# ADC.net
KiCad netlist of a schematic drawn in Altium Designer
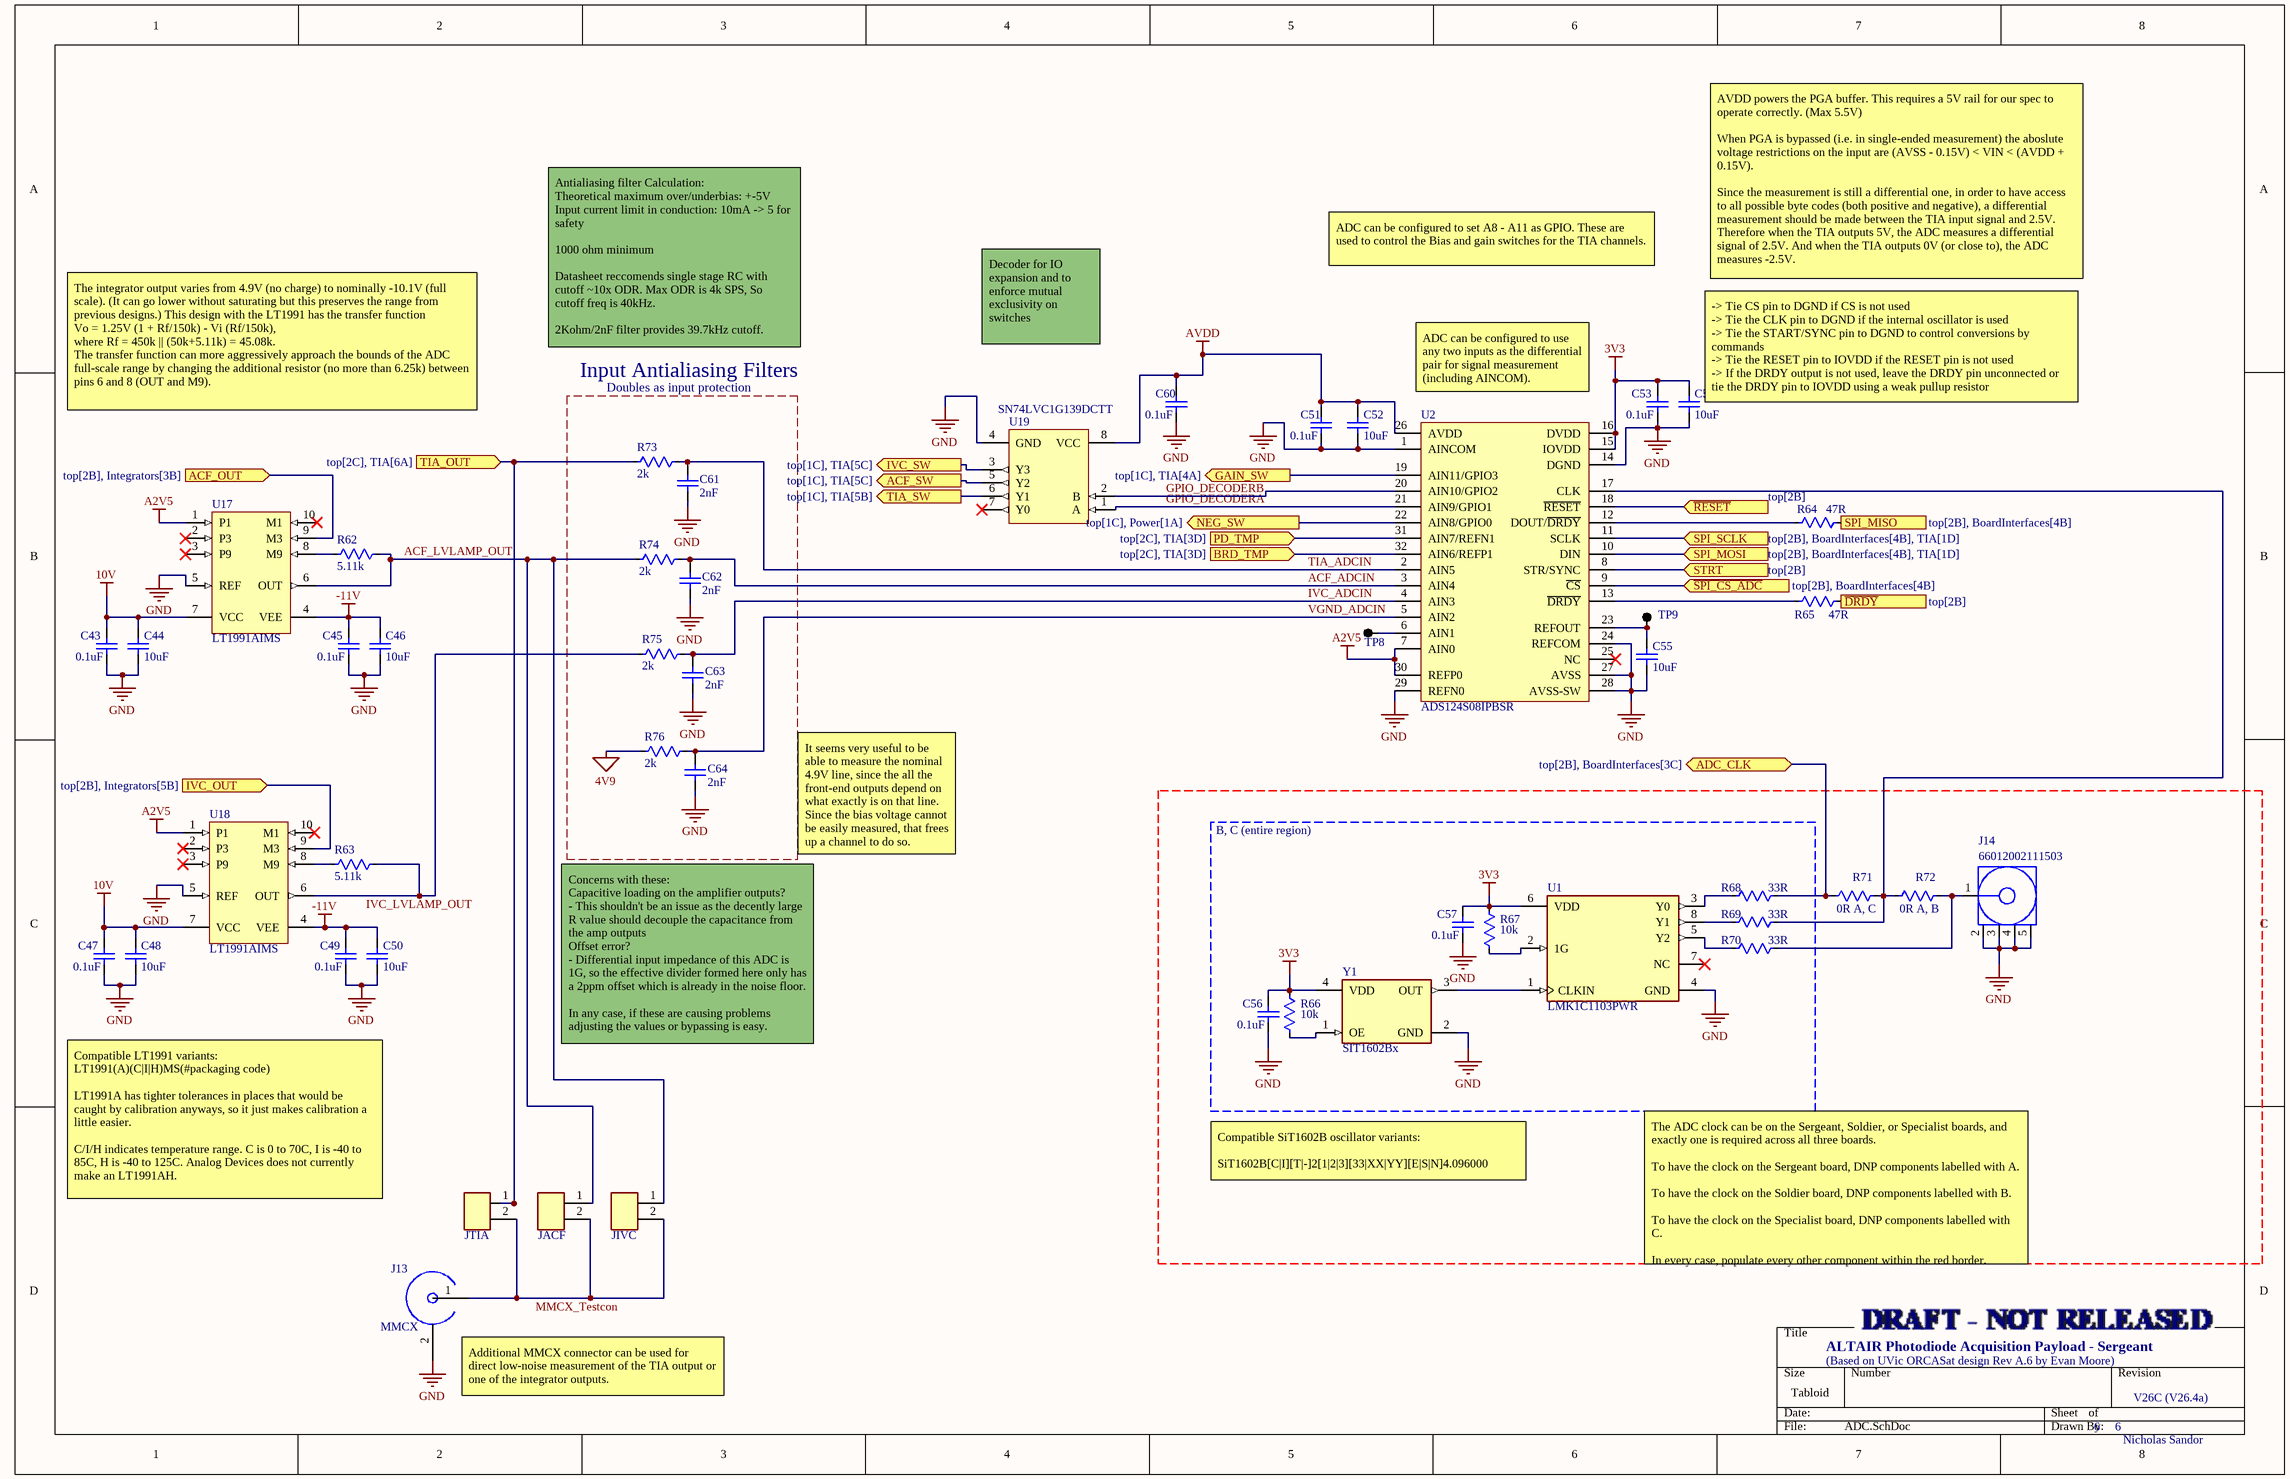
[diagram p0: ADC.SchDoc]

(export (version "E")
  (design (tool "Eeschema 10.0.6"))
  (components
    (comp (ref "C43")
      (value "0.1uF")
      (footprint "CAP 0603 NON-IPC KEMET X7R")
      (description "Kemet C0603C104K5RACAUTO - Cap Ceramic 0.1uF 50V X7R 10% 0603 125C Paper T/R")
      (fields (field (name "MF") "Kemet") (field (name "MP") "C0603C104K5RACAUTO"))
      (libsource (lib "ALTAIR_PD_Capacitors") (part "CAP"))
    )
    (comp (ref "C44")
      (value "10uF")
      (footprint "CAP 0805 IPC MID DENSITY")
      (description "Murata GRM21BR61E106KA73L - Cap Ceramic 10uF 10% 25V X5R 0805")
      (fields (field (name "MF") "Murata") (field (name "MP") "GRM21BR61E106KA73L"))
      (libsource (lib "ALTAIR_PD_Capacitors") (part "CAP"))
    )
    (comp (ref "C45")
      (value "0.1uF")
      (footprint "CAP 0603 NON-IPC KEMET X7R")
      (description "Kemet C0603C104K5RACAUTO - Cap Ceramic 0.1uF 50V X7R 10% 0603 125C Paper T/R")
      (fields (field (name "MF") "Kemet") (field (name "MP") "C0603C104K5RACAUTO"))
      (libsource (lib "ALTAIR_PD_Capacitors") (part "CAP"))
    )
    (comp (ref "C46")
      (value "10uF")
      (footprint "CAP 0805 IPC MID DENSITY")
      (description "Murata GRM21BR61E106KA73L - Cap Ceramic 10uF 10% 25V X5R 0805")
      (fields (field (name "MF") "Murata") (field (name "MP") "GRM21BR61E106KA73L"))
      (libsource (lib "ALTAIR_PD_Capacitors") (part "CAP"))
    )
    (comp (ref "C47")
      (value "0.1uF")
      (footprint "CAP 0603 NON-IPC KEMET X7R")
      (description "Kemet C0603C104K5RACAUTO - Cap Ceramic 0.1uF 50V X7R 10% 0603 125C Paper T/R")
      (fields (field (name "MF") "Kemet") (field (name "MP") "C0603C104K5RACAUTO"))
      (libsource (lib "ALTAIR_PD_Capacitors") (part "CAP"))
    )
    (comp (ref "C48")
      (value "10uF")
      (footprint "CAP 0805 IPC MID DENSITY")
      (description "Murata GRM21BR61E106KA73L - Cap Ceramic 10uF 10% 25V X5R 0805")
      (fields (field (name "MF") "Murata") (field (name "MP") "GRM21BR61E106KA73L"))
      (libsource (lib "ALTAIR_PD_Capacitors") (part "CAP"))
    )
    (comp (ref "C49")
      (value "0.1uF")
      (footprint "CAP 0603 NON-IPC KEMET X7R")
      (description "Kemet C0603C104K5RACAUTO - Cap Ceramic 0.1uF 50V X7R 10% 0603 125C Paper T/R")
      (fields (field (name "MF") "Kemet") (field (name "MP") "C0603C104K5RACAUTO"))
      (libsource (lib "ALTAIR_PD_Capacitors") (part "CAP"))
    )
    (comp (ref "C50")
      (value "10uF")
      (footprint "CAP 0805 IPC MID DENSITY")
      (description "Murata GRM21BR61E106KA73L - Cap Ceramic 10uF 10% 25V X5R 0805")
      (fields (field (name "MF") "Murata") (field (name "MP") "GRM21BR61E106KA73L"))
      (libsource (lib "ALTAIR_PD_Capacitors") (part "CAP"))
    )
    (comp (ref "C51")
      (value "0.1uF")
      (footprint "CAP 0603 IPC MID DENSITY")
      (description "Kemet C0603C104K5RACAUTO - Cap Ceramic 0.1uF 50V X7R 10% 0603 125C Paper T/R")
      (fields (field (name "MF") "Kemet") (field (name "MP") "C0603C104K5RACAUTO"))
      (libsource (lib "ALTAIR_PD_Capacitors") (part "CAP"))
    )
    (comp (ref "C52")
      (value "10uF")
      (footprint "CAP 0805 IPC MID DENSITY")
      (description "Murata GRM21BR61E106KA73L - Cap Ceramic 10uF 10% 25V X5R 0805")
      (fields (field (name "MF") "Murata") (field (name "MP") "GRM21BR61E106KA73L"))
      (libsource (lib "ALTAIR_PD_Capacitors") (part "CAP"))
    )
    (comp (ref "C53")
      (value "0.1uF")
      (footprint "CAP 0603 IPC MID DENSITY")
      (description "Kemet C0603C104K5RACAUTO - Cap Ceramic 0.1uF 50V X7R 10% 0603 125C Paper T/R")
      (fields (field (name "MF") "Kemet") (field (name "MP") "C0603C104K5RACAUTO"))
      (libsource (lib "ALTAIR_PD_Capacitors") (part "CAP"))
    )
    (comp (ref "C54")
      (value "10uF")
      (footprint "CAP 0805 IPC MID DENSITY")
      (description "Murata GRM21BR61E106KA73L - Cap Ceramic 10uF 10% 25V X5R 0805")
      (fields (field (name "MF") "Murata") (field (name "MP") "GRM21BR61E106KA73L"))
      (libsource (lib "ALTAIR_PD_Capacitors") (part "CAP"))
    )
    (comp (ref "C55")
      (value "10uF")
      (footprint "CAP 0805 IPC MID DENSITY")
      (description "Murata GRM21BR61E106KA73L - Cap Ceramic 10uF 10% 25V X5R 0805")
      (fields (field (name "MF") "Murata") (field (name "MP") "GRM21BR61E106KA73L"))
      (libsource (lib "ALTAIR_PD_Capacitors") (part "CAP"))
    )
    (comp (ref "C56")
      (value "0.1uF")
      (footprint "CAP 0603 IPC MID DENSITY")
      (description "Kemet C0603C104K5RACAUTO - Cap Ceramic 0.1uF 50V X7R 10% 0603 125C Paper T/R")
      (fields (field (name "MF") "Kemet") (field (name "MP") "C0603C104K5RACAUTO"))
      (libsource (lib "ALTAIR_PD_Capacitors") (part "CAP"))
    )
    (comp (ref "C57")
      (value "0.1uF")
      (footprint "CAP 0603 IPC MID DENSITY")
      (description "Kemet C0603C104K5RACAUTO - Cap Ceramic 0.1uF 50V X7R 10% 0603 125C Paper T/R")
      (fields (field (name "MF") "Kemet") (field (name "MP") "C0603C104K5RACAUTO"))
      (libsource (lib "ALTAIR_PD_Capacitors") (part "CAP"))
    )
    (comp (ref "C60")
      (value "0.1uF")
      (footprint "CAP 0603 IPC MID DENSITY")
      (description "Kemet C0603C104K5RACAUTO - Cap Ceramic 0.1uF 50V X7R 10% 0603 125C Paper T/R")
      (fields (field (name "MF") "Kemet") (field (name "MP") "C0603C104K5RACAUTO"))
      (libsource (lib "ALTAIR_PD_Capacitors") (part "CAP"))
    )
    (comp (ref "C61")
      (value "2nF")
      (footprint "CAP 0603 IPC MID DENSITY")
      (description "Cap, Nonpolar, Any, Must choose footprint manually")
      (libsource (lib "ALTAIR_PD_Capacitors") (part "CAP"))
    )
    (comp (ref "C62")
      (value "2nF")
      (footprint "CAP 0603 IPC MID DENSITY")
      (description "Cap, Nonpolar, Any, Must choose footprint manually")
      (libsource (lib "ALTAIR_PD_Capacitors") (part "CAP"))
    )
    (comp (ref "C63")
      (value "2nF")
      (footprint "CAP 0603 IPC MID DENSITY")
      (description "Cap, Nonpolar, Any, Must choose footprint manually")
      (libsource (lib "ALTAIR_PD_Capacitors") (part "CAP"))
    )
    (comp (ref "C64")
      (value "2nF")
      (footprint "CAP 0603 IPC MID DENSITY")
      (description "Cap, Nonpolar, Any, Must choose footprint manually")
      (libsource (lib "ALTAIR_PD_Capacitors") (part "CAP"))
    )
    (comp (ref "J13")
      (value "MMCX")
      (footprint "COAX MMCX SMD")
      (description "Conn MMCX F 50Ohm Solder ST SMD Gold Tray")
      (fields (field (name "MF") "Molex") (field (name "MP") "0734152061"))
      (libsource (lib "ALTAIR_PD_Coaxial") (part "MMCX_recp"))
    )
    (comp (ref "J14")
      (value "66012002111503")
      (footprint "COAX MMCX THT")
      (description "Rf Coaxial, Mmcx Jack, 50 Ohm, Pcb Rohs Compliant: Yes ¦Wurth Elektronik 66012002111503")
      (fields (field (name "MF") "Wurth Elektronik"))
      (libsource (lib "ALTAIR_PD_Coaxial") (part "CMP-207975-000001-3"))
    )
    (comp (ref "JACF")
      (value "JACF")
      (footprint "ALTAIR_PD_Headers:JUMPER 2POS 1MM PITCH THT")
      (description "2x1 Header THT 1mm Pitch")
      (fields
        (field (name "MF") "GCT (GLOBAL CONNECTOR TECHNOLOGY)")
        (field (name "MP") "BC020-02-A-0200-0300-L-G")
      )
      (libsource (lib "ALTAIR_PD_Headers") (part "BC020-02-A-0200-0300-L-G"))
    )
    (comp (ref "JIVC")
      (value "JIVC")
      (footprint "ALTAIR_PD_Headers:JUMPER 2POS 1MM PITCH THT")
      (description "2x1 Header THT 1mm Pitch")
      (fields
        (field (name "MF") "GCT (GLOBAL CONNECTOR TECHNOLOGY)")
        (field (name "MP") "BC020-02-A-0200-0300-L-G")
      )
      (libsource (lib "ALTAIR_PD_Headers") (part "BC020-02-A-0200-0300-L-G"))
    )
    (comp (ref "JTIA")
      (value "JTIA")
      (footprint "ALTAIR_PD_Headers:JUMPER 2POS 1MM PITCH THT")
      (description "2x1 Header THT 1mm Pitch")
      (fields
        (field (name "MF") "GCT (GLOBAL CONNECTOR TECHNOLOGY)")
        (field (name "MP") "BC020-02-A-0200-0300-L-G")
      )
      (libsource (lib "ALTAIR_PD_Headers") (part "BC020-02-A-0200-0300-L-G"))
    )
    (comp (ref "R62")
      (value "5.11k")
      (footprint "RES 0402 IPC MID DENSITY")
      (description "Panasonic ERA-2AEB5111X - Res 5.11k 0.1% 1/16W SMD 0402")
      (fields (field (name "MF") "Panasonic Electronic Components") (field (name "MP") "ERA-2AEB5111X"))
      (libsource (lib "ALTAIR_PD_Resistors") (part "RES"))
    )
    (comp (ref "R63")
      (value "5.11k")
      (footprint "RES 0402 IPC MID DENSITY")
      (description "Panasonic ERA-2AEB5111X - Res 5.11k 0.1% 1/16W SMD 0402")
      (fields (field (name "MF") "Panasonic Electronic Components") (field (name "MP") "ERA-2AEB5111X"))
      (libsource (lib "ALTAIR_PD_Resistors") (part "RES"))
    )
    (comp (ref "R64")
      (value "47R")
      (footprint "RES 0402 NON-IPC SEI")
      (description "Stackpole RMCF0402JT47R0 - Res 47Ohm 5% 0.063W 0402 Thick Film AEC-Q200 compliant")
      (fields (field (name "MF") "Stackpole Electronics Inc.") (field (name "MP") "RMCF0402JT47R0"))
      (libsource (lib "ALTAIR_PD_Resistors") (part "RES"))
    )
    (comp (ref "R65")
      (value "47R")
      (footprint "RES 0402 NON-IPC SEI")
      (description "Stackpole RMCF0402JT47R0 - Res 47Ohm 5% 0.063W 0402 Thick Film AEC-Q200 compliant")
      (fields (field (name "MF") "Stackpole Electronics Inc.") (field (name "MP") "RMCF0402JT47R0"))
      (libsource (lib "ALTAIR_PD_Resistors") (part "RES"))
    )
    (comp (ref "R66")
      (value "10k")
      (footprint "RES 0603 IPC MID DENSITY")
      (description "Vishay CRCW060310K0FKEA SMD 0603 10k, CRCW e3 Series, 75V, thick film, 100mW")
      (fields (field (name "MF") "Vishay Dale") (field (name "MP") "CRCW060310K0FKEA"))
      (libsource (lib "ALTAIR_PD_Resistors") (part "RES"))
    )
    (comp (ref "R67")
      (value "10k")
      (footprint "RES 0603 IPC MID DENSITY")
      (description "Vishay CRCW060310K0FKEA SMD 0603 10k, CRCW e3 Series, 75V, thick film, 100mW")
      (fields (field (name "MF") "Vishay Dale") (field (name "MP") "CRCW060310K0FKEA"))
      (libsource (lib "ALTAIR_PD_Resistors") (part "RES"))
    )
    (comp (ref "R68")
      (value "33R")
      (footprint "RES 0402 NON-IPC YAGEO")
      (description "Yageo RC0402FR-0733RL - Res 33Ohm 1% 1/16W 0402")
      (fields (field (name "MF") "YAGEO") (field (name "MP") "RC0402FR-0733RL"))
      (libsource (lib "ALTAIR_PD_Resistors") (part "RES"))
    )
    (comp (ref "R69")
      (value "33R")
      (footprint "RES 0402 NON-IPC YAGEO")
      (description "Yageo RC0402FR-0733RL - Res 33Ohm 1% 1/16W 0402")
      (fields (field (name "MF") "YAGEO") (field (name "MP") "RC0402FR-0733RL"))
      (libsource (lib "ALTAIR_PD_Resistors") (part "RES"))
    )
    (comp (ref "R70")
      (value "33R")
      (footprint "RES 0402 NON-IPC YAGEO")
      (description "Yageo RC0402FR-0733RL - Res 33Ohm 1% 1/16W 0402")
      (fields (field (name "MF") "YAGEO") (field (name "MP") "RC0402FR-0733RL"))
      (libsource (lib "ALTAIR_PD_Resistors") (part "RES"))
    )
    (comp (ref "R71")
      (value "0R A, C")
      (footprint "RES 0402 IPC MID DENSITY")
      (description "Yageo RC0402JR-070RL - Res 0 Ohms 1/16W SMD 0402")
      (fields (field (name "MF") "YAGEO") (field (name "MP") "RC0402JR-070RL"))
      (libsource (lib "ALTAIR_PD_Resistors") (part "RES"))
    )
    (comp (ref "R72")
      (value "0R A, B")
      (footprint "RES 0402 IPC MID DENSITY")
      (description "Yageo RC0402JR-070RL - Res 0 Ohms 1/16W SMD 0402")
      (fields (field (name "MF") "YAGEO") (field (name "MP") "RC0402JR-070RL"))
      (libsource (lib "ALTAIR_PD_Resistors") (part "RES"))
    )
    (comp (ref "R73")
      (value "2k")
      (footprint "RES 0402 IPC MID DENSITY")
      (description "Res, Any, Manually select footprint")
      (libsource (lib "ALTAIR_PD_Resistors") (part "RES"))
    )
    (comp (ref "R74")
      (value "2k")
      (footprint "RES 0402 IPC MID DENSITY")
      (description "Res, Any, Manually select footprint")
      (libsource (lib "ALTAIR_PD_Resistors") (part "RES"))
    )
    (comp (ref "R75")
      (value "2k")
      (footprint "RES 0402 IPC MID DENSITY")
      (description "Res, Any, Manually select footprint")
      (libsource (lib "ALTAIR_PD_Resistors") (part "RES"))
    )
    (comp (ref "R76")
      (value "2k")
      (footprint "RES 0402 IPC MID DENSITY")
      (description "Res, Any, Manually select footprint")
      (libsource (lib "ALTAIR_PD_Resistors") (part "RES"))
    )
    (comp (ref "TP8")
      (value "Testpoint")
      (footprint "TESTPOINT THT")
      (libsource (lib "ALTAIR_PD_Testpoint") (part "Testpoint"))
    )
    (comp (ref "TP9")
      (value "Testpoint")
      (footprint "TESTPOINT THT")
      (libsource (lib "ALTAIR_PD_Testpoint") (part "Testpoint"))
    )
    (comp (ref "U1")
      (value "LMK1C1103PWR")
      (footprint "8-TSSOP 0.65MM PITCH 4.4MM WIDTH IPC MID DENSITY")
      (description "LVCMOS CLOCK BUFFER 3-CHANNEL")
      (fields (field (name "MF") "Texas Instruments"))
      (libsource (lib "ALTAIR_PD_ClockParts") (part "LMK1C1103PWR"))
    )
    (comp (ref "U2")
      (value "ADS124S08IPBSR")
      (footprint "32TQFP 7X7MM IPC LOW DENSITY")
      (description "24BIT ADC Delta-Sigma 4k samples/s PGA V-reference")
      (fields (field (name "MF") "Texas Instruments"))
      (libsource (lib "ALTAIR_PD_ADCs") (part "ADS124S08IPBSR"))
    )
    (comp (ref "U17")
      (value "LT1991AIMS")
      (footprint "10-SOP 0.5MM PITCH 3MM WIDTH IPC HIGH DENSITY")
      (fields
        (field (name "MF") "Linear Technology")
        (field (name "MP") "LT1991AIMS#PBF")
        (field (name "LINEAR TECHNOLOGY PART NUMBER") "LT1991")
      )
      (libsource (lib "ALTAIR_PD_Amplifiers") (part "LT1991IMS#TRPBF"))
    )
    (comp (ref "U18")
      (value "LT1991AIMS")
      (footprint "10-SOP 0.5MM PITCH 3MM WIDTH IPC HIGH DENSITY")
      (fields
        (field (name "MF") "Linear Technology")
        (field (name "MP") "LT1991AIMS#PBF")
        (field (name "LINEAR TECHNOLOGY PART NUMBER") "LT1991")
      )
      (libsource (lib "ALTAIR_PD_Amplifiers") (part "LT1991IMS#TRPBF"))
    )
    (comp (ref "U19")
      (value "SN74LVC1G139DCTT")
      (footprint "DCT0008A_L")
      (description "2-Line-to-4-Line Decoder, DCT0008A, SMALL T&R")
      (fields
        (field (name "MANUFACTURER") "Texas Instruments")
        (field (name "GENERIC PART NUMBER") "SN74LVC1G139")
      )
      (libsource (lib "Altium Content Vault") (part "TI-SN74LVC1G139-8"))
    )
    (comp (ref "Y1")
      (value "SIT1602Bx")
      (footprint "4PQFN NON-IPC SITIME")
      (description "MEMS OSC XO 4.096MHZ H/LVCMOS")
      (fields (field (name "MF") "SiTime") (field (name "MP") "SiT1602BC-21-XXN-4.096000"))
      (libsource (lib "ALTAIR_PD_ClockParts") (part "SIT1602Bx"))
    )
  )
  (nets
    (net (code "1") (name "-11V") (class "Default")
      (node (ref "C45") (pin "2") (pinfunction "2_2") (pintype "passive"))
      (node (ref "C46") (pin "2") (pinfunction "2_2") (pintype "passive"))
      (node (ref "C49") (pin "2") (pinfunction "2_2") (pintype "passive"))
      (node (ref "C50") (pin "2") (pinfunction "2_2") (pintype "passive"))
      (node (ref "U17") (pin "4") (pinfunction "VEE_4") (pintype "power_in"))
      (node (ref "U18") (pin "4") (pinfunction "VEE_4") (pintype "power_in"))
    )
    (net (code "2") (name "/ACF_ADCIN") (class "Default")
      (node (ref "C62") (pin "2") (pinfunction "2_2") (pintype "passive"))
      (node (ref "R74") (pin "2") (pinfunction "2_2") (pintype "passive"))
      (node (ref "U2") (pin "3") (pinfunction "AIN4_3") (pintype "passive"))
    )
    (net (code "3") (name "/ACF_LVLAMP_OUT") (class "Default")
      (node (ref "JACF") (pin "1") (pinfunction "1_1") (pintype "passive"))
      (node (ref "JIVC") (pin "1") (pinfunction "1_1") (pintype "passive"))
      (node (ref "R62") (pin "2") (pinfunction "2_2") (pintype "passive"))
      (node (ref "R74") (pin "1") (pinfunction "1_1") (pintype "passive"))
      (node (ref "U17") (pin "6") (pinfunction "OUT_6") (pintype "output"))
    )
    (net (code "4") (name "/ACF_OUT") (class "Default")
      (node (ref "U17") (pin "9") (pinfunction "M3_9") (pintype "input"))
    )
    (net (code "5") (name "/ACF_SW") (class "Default")
      (node (ref "U19") (pin "5") (pinfunction "Y2_5") (pintype "output"))
    )
    (net (code "6") (name "/ADC_CLK") (class "Default")
      (node (ref "R68") (pin "1") (pinfunction "1_1") (pintype "passive"))
      (node (ref "R71") (pin "2") (pinfunction "2_2") (pintype "passive"))
    )
    (net (code "7") (name "/BRD_TMP") (class "Default")
      (node (ref "U2") (pin "32") (pinfunction "AIN6/REFP1_32") (pintype "passive"))
    )
    (net (code "8") (name "/DRDY") (class "Default")
      (node (ref "R65") (pin "2") (pinfunction "2_2") (pintype "passive"))
    )
    (net (code "9") (name "/GAIN_SW") (class "Default")
      (node (ref "U2") (pin "19") (pinfunction "AIN11/GPIO3_19") (pintype "passive"))
    )
    (net (code "10") (name "/GPIO_DECODERA") (class "Default")
      (node (ref "U19") (pin "1") (pinfunction "A_1") (pintype "input"))
      (node (ref "U2") (pin "21") (pinfunction "AIN9/GPIO1_21") (pintype "passive"))
    )
    (net (code "11") (name "/GPIO_DECODERB") (class "Default")
      (node (ref "U19") (pin "2") (pinfunction "B_2") (pintype "input"))
      (node (ref "U2") (pin "20") (pinfunction "AIN10/GPIO2_20") (pintype "passive"))
    )
    (net (code "12") (name "/IVC_ADCIN") (class "Default")
      (node (ref "C63") (pin "2") (pinfunction "2_2") (pintype "passive"))
      (node (ref "R75") (pin "2") (pinfunction "2_2") (pintype "passive"))
      (node (ref "U2") (pin "4") (pinfunction "AIN3_4") (pintype "passive"))
    )
    (net (code "13") (name "/IVC_LVLAMP_OUT") (class "Default")
      (node (ref "R63") (pin "2") (pinfunction "2_2") (pintype "passive"))
      (node (ref "R75") (pin "1") (pinfunction "1_1") (pintype "passive"))
      (node (ref "U18") (pin "6") (pinfunction "OUT_6") (pintype "output"))
    )
    (net (code "14") (name "/IVC_OUT") (class "Default")
      (node (ref "U18") (pin "9") (pinfunction "M3_9") (pintype "input"))
    )
    (net (code "15") (name "/IVC_SW") (class "Default")
      (node (ref "U19") (pin "3") (pinfunction "Y3_3") (pintype "output"))
    )
    (net (code "16") (name "/MMCX_Testcon") (class "Default")
      (node (ref "J13") (pin "1") (pinfunction "1_1") (pintype "passive"))
      (node (ref "JACF") (pin "2") (pinfunction "2_2") (pintype "passive"))
      (node (ref "JIVC") (pin "2") (pinfunction "2_2") (pintype "passive"))
      (node (ref "JTIA") (pin "2") (pinfunction "2_2") (pintype "passive"))
    )
    (net (code "17") (name "/NEG_SW") (class "Default")
      (node (ref "U2") (pin "22") (pinfunction "AIN8/GPIO0_22") (pintype "passive"))
    )
    (net (code "18") (name "/PD_TMP") (class "Default")
      (node (ref "U2") (pin "31") (pinfunction "AIN7/REFN1_31") (pintype "passive"))
    )
    (net (code "19") (name "/RESET") (class "Default")
      (node (ref "U2") (pin "18") (pinfunction "~{RESET}_18") (pintype "passive"))
    )
    (net (code "20") (name "/SPI_CS_ADC") (class "Default")
      (node (ref "U2") (pin "9") (pinfunction "~{CS}_9") (pintype "passive"))
    )
    (net (code "21") (name "/SPI_MISO") (class "Default")
      (node (ref "R64") (pin "2") (pinfunction "2_2") (pintype "passive"))
    )
    (net (code "22") (name "/SPI_MOSI") (class "Default")
      (node (ref "U2") (pin "10") (pinfunction "DIN_10") (pintype "passive"))
    )
    (net (code "23") (name "/SPI_SCLK") (class "Default")
      (node (ref "U2") (pin "11") (pinfunction "SCLK_11") (pintype "passive"))
    )
    (net (code "24") (name "/STRT") (class "Default")
      (node (ref "U2") (pin "8") (pinfunction "STR/SYNC_8") (pintype "passive"))
    )
    (net (code "25") (name "/TIA_ADCIN") (class "Default")
      (node (ref "C61") (pin "2") (pinfunction "2_2") (pintype "passive"))
      (node (ref "R73") (pin "2") (pinfunction "2_2") (pintype "passive"))
      (node (ref "U2") (pin "2") (pinfunction "AIN5_2") (pintype "passive"))
    )
    (net (code "26") (name "/TIA_OUT") (class "Default")
      (node (ref "JTIA") (pin "1") (pinfunction "1_1") (pintype "passive"))
      (node (ref "R73") (pin "1") (pinfunction "1_1") (pintype "passive"))
    )
    (net (code "27") (name "/TIA_SW") (class "Default")
      (node (ref "U19") (pin "6") (pinfunction "Y1_6") (pintype "output"))
    )
    (net (code "28") (name "/VGND_ADCIN") (class "Default")
      (node (ref "C64") (pin "2") (pinfunction "2_2") (pintype "passive"))
      (node (ref "R76") (pin "2") (pinfunction "2_2") (pintype "passive"))
      (node (ref "U2") (pin "5") (pinfunction "AIN2_5") (pintype "passive"))
    )
    (net (code "29") (name "3V3") (class "Default")
      (node (ref "C53") (pin "2") (pinfunction "2_2") (pintype "passive"))
      (node (ref "C54") (pin "2") (pinfunction "2_2") (pintype "passive"))
      (node (ref "C56") (pin "2") (pinfunction "2_2") (pintype "passive"))
      (node (ref "C57") (pin "2") (pinfunction "2_2") (pintype "passive"))
      (node (ref "R66") (pin "2") (pinfunction "2_2") (pintype "passive"))
      (node (ref "R67") (pin "2") (pinfunction "2_2") (pintype "passive"))
      (node (ref "U1") (pin "6") (pinfunction "VDD_6") (pintype "power_in"))
      (node (ref "U2") (pin "15") (pinfunction "IOVDD_15") (pintype "passive"))
      (node (ref "U2") (pin "16") (pinfunction "DVDD_16") (pintype "passive"))
      (node (ref "Y1") (pin "4") (pinfunction "VDD_4") (pintype "power_in"))
    )
    (net (code "30") (name "4V9") (class "Default")
      (node (ref "R76") (pin "1") (pinfunction "1_1") (pintype "passive"))
    )
    (net (code "31") (name "10V") (class "Default")
      (node (ref "C43") (pin "2") (pinfunction "2_2") (pintype "passive"))
      (node (ref "C44") (pin "2") (pinfunction "2_2") (pintype "passive"))
      (node (ref "C47") (pin "2") (pinfunction "2_2") (pintype "passive"))
      (node (ref "C48") (pin "2") (pinfunction "2_2") (pintype "passive"))
      (node (ref "U17") (pin "7") (pinfunction "VCC_7") (pintype "power_in"))
      (node (ref "U18") (pin "7") (pinfunction "VCC_7") (pintype "power_in"))
    )
    (net (code "32") (name "A2V5") (class "Default")
      (node (ref "U17") (pin "1") (pinfunction "P1_1") (pintype "input"))
      (node (ref "U18") (pin "1") (pinfunction "P1_1") (pintype "input"))
      (node (ref "U2") (pin "30") (pinfunction "REFP0_30") (pintype "passive"))
      (node (ref "U2") (pin "7") (pinfunction "AIN0_7") (pintype "passive"))
    )
    (net (code "33") (name "AVDD") (class "Default")
      (node (ref "C51") (pin "2") (pinfunction "2_2") (pintype "passive"))
      (node (ref "C52") (pin "2") (pinfunction "2_2") (pintype "passive"))
      (node (ref "C60") (pin "2") (pinfunction "2_2") (pintype "passive"))
      (node (ref "U19") (pin "8") (pinfunction "VCC_8") (pintype "power_in"))
      (node (ref "U2") (pin "26") (pinfunction "AVDD_26") (pintype "passive"))
    )
    (net (code "34") (name "GND") (class "Default")
      (node (ref "C43") (pin "1") (pinfunction "1_1") (pintype "passive"))
      (node (ref "C44") (pin "1") (pinfunction "1_1") (pintype "passive"))
      (node (ref "C45") (pin "1") (pinfunction "1_1") (pintype "passive"))
      (node (ref "C46") (pin "1") (pinfunction "1_1") (pintype "passive"))
      (node (ref "C47") (pin "1") (pinfunction "1_1") (pintype "passive"))
      (node (ref "C48") (pin "1") (pinfunction "1_1") (pintype "passive"))
      (node (ref "C49") (pin "1") (pinfunction "1_1") (pintype "passive"))
      (node (ref "C50") (pin "1") (pinfunction "1_1") (pintype "passive"))
      (node (ref "C51") (pin "1") (pinfunction "1_1") (pintype "passive"))
      (node (ref "C52") (pin "1") (pinfunction "1_1") (pintype "passive"))
      (node (ref "C53") (pin "1") (pinfunction "1_1") (pintype "passive"))
      (node (ref "C54") (pin "1") (pinfunction "1_1") (pintype "passive"))
      (node (ref "C55") (pin "1") (pinfunction "1_1") (pintype "passive"))
      (node (ref "C56") (pin "1") (pinfunction "1_1") (pintype "passive"))
      (node (ref "C57") (pin "1") (pinfunction "1_1") (pintype "passive"))
      (node (ref "C60") (pin "1") (pinfunction "1_1") (pintype "passive"))
      (node (ref "C61") (pin "1") (pinfunction "1_1") (pintype "passive"))
      (node (ref "C62") (pin "1") (pinfunction "1_1") (pintype "passive"))
      (node (ref "C63") (pin "1") (pinfunction "1_1") (pintype "passive"))
      (node (ref "C64") (pin "1") (pinfunction "1_1") (pintype "passive"))
      (node (ref "J13") (pin "2") (pinfunction "2_2") (pintype "passive"))
      (node (ref "J14") (pin "2") (pinfunction "GND_2") (pintype "passive"))
      (node (ref "J14") (pin "3") (pinfunction "GND_3") (pintype "passive"))
      (node (ref "J14") (pin "4") (pinfunction "GND_4") (pintype "passive"))
      (node (ref "J14") (pin "5") (pinfunction "GND_5") (pintype "passive"))
      (node (ref "U1") (pin "4") (pinfunction "GND_4") (pintype "power_in"))
      (node (ref "U17") (pin "5") (pinfunction "REF_5") (pintype "input"))
      (node (ref "U18") (pin "5") (pinfunction "REF_5") (pintype "input"))
      (node (ref "U19") (pin "4") (pinfunction "GND_4") (pintype "power_in"))
      (node (ref "U2") (pin "1") (pinfunction "AINCOM_1") (pintype "passive"))
      (node (ref "U2") (pin "14") (pinfunction "DGND_14") (pintype "passive"))
      (node (ref "U2") (pin "24") (pinfunction "REFCOM_24") (pintype "passive"))
      (node (ref "U2") (pin "27") (pinfunction "AVSS_27") (pintype "passive"))
      (node (ref "U2") (pin "28") (pinfunction "AVSS-SW_28") (pintype "passive"))
      (node (ref "U2") (pin "29") (pinfunction "REFN0_29") (pintype "passive"))
      (node (ref "Y1") (pin "2") (pinfunction "GND_2") (pintype "power_in"))
    )
    (net (code "35") (name "Net-(J14-Signal)") (class "Default")
      (node (ref "J14") (pin "1") (pinfunction "Signal_1") (pintype "passive"))
      (node (ref "R70") (pin "1") (pinfunction "1_1") (pintype "passive"))
      (node (ref "R72") (pin "1") (pinfunction "1_1") (pintype "passive"))
    )
    (net (code "36") (name "Net-(U1-1G)") (class "Default")
      (node (ref "R67") (pin "1") (pinfunction "1_1") (pintype "passive"))
      (node (ref "U1") (pin "2") (pinfunction "1G_2") (pintype "input"))
    )
    (net (code "37") (name "Net-(U1-CLKIN)") (class "Default")
      (node (ref "U1") (pin "1") (pinfunction "CLKIN_1") (pintype "input"))
      (node (ref "Y1") (pin "3") (pinfunction "OUT_3") (pintype "output"))
    )
    (net (code "38") (name "Net-(U1-Y0)") (class "Default")
      (node (ref "R68") (pin "2") (pinfunction "2_2") (pintype "passive"))
      (node (ref "U1") (pin "3") (pinfunction "Y0_3") (pintype "output"))
    )
    (net (code "39") (name "Net-(U1-Y1)") (class "Default")
      (node (ref "R69") (pin "2") (pinfunction "2_2") (pintype "passive"))
      (node (ref "U1") (pin "8") (pinfunction "Y1_8") (pintype "output"))
    )
    (net (code "40") (name "Net-(U1-Y2)") (class "Default")
      (node (ref "R70") (pin "2") (pinfunction "2_2") (pintype "passive"))
      (node (ref "U1") (pin "5") (pinfunction "Y2_5") (pintype "output"))
    )
    (net (code "41") (name "Net-(U2-AIN1)") (class "Default")
      (node (ref "TP8") (pin "1") (pinfunction "1_1") (pintype "passive"))
      (node (ref "U2") (pin "6") (pinfunction "AIN1_6") (pintype "passive"))
    )
    (net (code "42") (name "Net-(U2-CLK)") (class "Default")
      (node (ref "R69") (pin "1") (pinfunction "1_1") (pintype "passive"))
      (node (ref "R71") (pin "1") (pinfunction "1_1") (pintype "passive"))
      (node (ref "R72") (pin "2") (pinfunction "2_2") (pintype "passive"))
      (node (ref "U2") (pin "17") (pinfunction "CLK_17") (pintype "passive"))
    )
    (net (code "43") (name "Net-(U2-DOUT{slash}~{DRDY})") (class "Default")
      (node (ref "R64") (pin "1") (pinfunction "1_1") (pintype "passive"))
      (node (ref "U2") (pin "12") (pinfunction "DOUT/~{DRDY}_12") (pintype "passive"))
    )
    (net (code "44") (name "Net-(U2-REFOUT)") (class "Default")
      (node (ref "C55") (pin "2") (pinfunction "2_2") (pintype "passive"))
      (node (ref "TP9") (pin "1") (pinfunction "1_1") (pintype "passive"))
      (node (ref "U2") (pin "23") (pinfunction "REFOUT_23") (pintype "passive"))
    )
    (net (code "45") (name "Net-(U2-~{DRDY})") (class "Default")
      (node (ref "R65") (pin "1") (pinfunction "1_1") (pintype "passive"))
      (node (ref "U2") (pin "13") (pinfunction "~{DRDY}_13") (pintype "passive"))
    )
    (net (code "46") (name "Net-(U17-M9)") (class "Default")
      (node (ref "R62") (pin "1") (pinfunction "1_1") (pintype "passive"))
      (node (ref "U17") (pin "8") (pinfunction "M9_8") (pintype "input"))
    )
    (net (code "47") (name "Net-(U18-M9)") (class "Default")
      (node (ref "R63") (pin "1") (pinfunction "1_1") (pintype "passive"))
      (node (ref "U18") (pin "8") (pinfunction "M9_8") (pintype "input"))
    )
    (net (code "48") (name "Net-(Y1-OE)") (class "Default")
      (node (ref "R66") (pin "1") (pinfunction "1_1") (pintype "passive"))
      (node (ref "Y1") (pin "1") (pinfunction "OE_1") (pintype "input"))
    )
    (net (code "49") (name "unconnected-(U1-NC-Pad7)") (class "Default")
      (node (ref "U1") (pin "7") (pinfunction "NC_7") (pintype "passive+no_connect"))
    )
    (net (code "50") (name "unconnected-(U2-NC-Pad25)") (class "Default")
      (node (ref "U2") (pin "25") (pinfunction "NC_25") (pintype "passive+no_connect"))
    )
    (net (code "51") (name "unconnected-(U17-M1-Pad10)") (class "Default")
      (node (ref "U17") (pin "10") (pinfunction "M1_10") (pintype "input+no_connect"))
    )
    (net (code "52") (name "unconnected-(U17-P3-Pad2)") (class "Default")
      (node (ref "U17") (pin "2") (pinfunction "P3_2") (pintype "input+no_connect"))
    )
    (net (code "53") (name "unconnected-(U17-P9-Pad3)") (class "Default")
      (node (ref "U17") (pin "3") (pinfunction "P9_3") (pintype "input+no_connect"))
    )
    (net (code "54") (name "unconnected-(U18-M1-Pad10)") (class "Default")
      (node (ref "U18") (pin "10") (pinfunction "M1_10") (pintype "input+no_connect"))
    )
    (net (code "55") (name "unconnected-(U18-P3-Pad2)") (class "Default")
      (node (ref "U18") (pin "2") (pinfunction "P3_2") (pintype "input+no_connect"))
    )
    (net (code "56") (name "unconnected-(U18-P9-Pad3)") (class "Default")
      (node (ref "U18") (pin "3") (pinfunction "P9_3") (pintype "input+no_connect"))
    )
    (net (code "57") (name "unconnected-(U19-Y0-Pad7)") (class "Default")
      (node (ref "U19") (pin "7") (pinfunction "Y0_7") (pintype "output+no_connect"))
    )
  )
)
